# SensorsActuators.net
KiCad netlist of a schematic drawn in Altium Designer
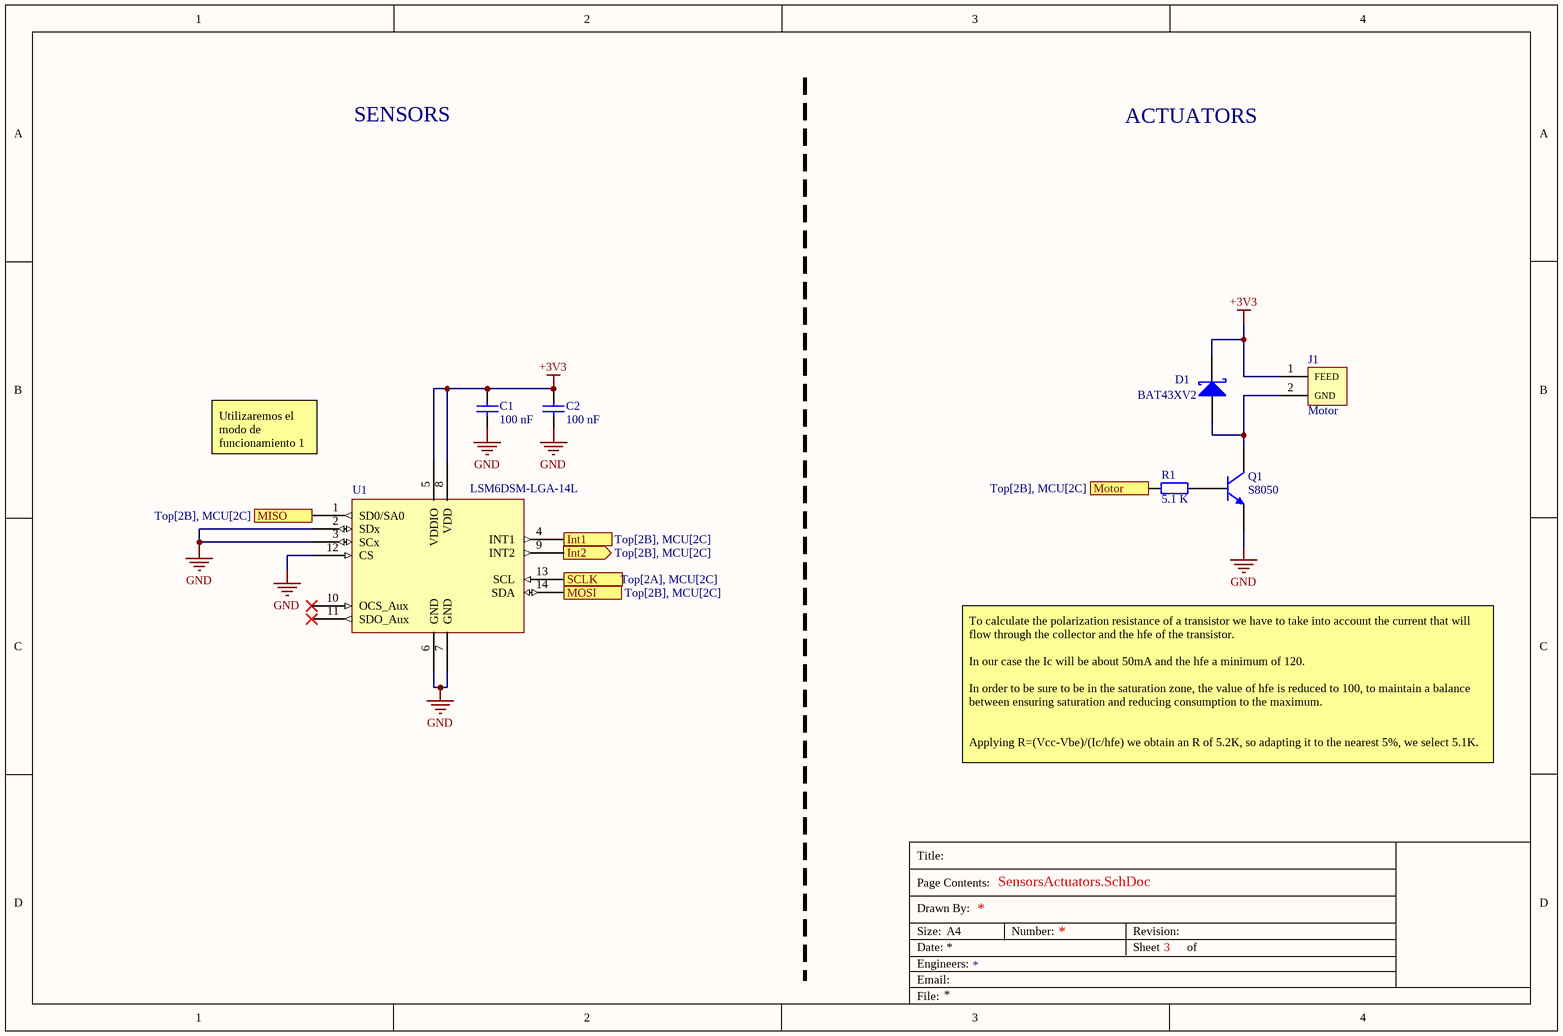
[diagram p0: SensorsActuators.SchDoc]

(export (version "E")
  (design (tool "Eeschema 10.0.6"))
  (components
    (comp (ref "C1")
      (value "100 nF")
      (footprint "C0402")
      (description "Capacitor")
      (libsource (lib "DEOP2324") (part "C"))
    )
    (comp (ref "C2")
      (value "100 nF")
      (footprint "C0402")
      (description "Capacitor")
      (libsource (lib "DEOP2324") (part "C"))
    )
    (comp (ref "D1")
      (value "BAT43XV2")
      (footprint "SOD_523")
      (description "Schottky Diode")
      (libsource (lib "DEOP2324") (part "D Schottky"))
    )
    (comp (ref "J1")
      (value "Motor")
      (footprint "Hand solder wire polarity")
      (libsource (lib "DEOP2324") (part "Motor"))
    )
    (comp (ref "Q1")
      (value "S8050")
      (footprint "SOT23")
      (description "NPN Bipolar Transistor")
      (libsource (lib "DEOP2324") (part "NPN"))
    )
    (comp (ref "R1")
      (value "5.1 K")
      (footprint "R0402")
      (description "Resistor")
      (libsource (lib "DEOP2324") (part "R"))
    )
    (comp (ref "U1")
      (value "LSM6DSM-LGA-14L")
      (footprint "LSM6DSM-LGA-14L-v2")
      (description "6-axis IMU, Accel&Gyro")
      (libsource (lib "DEOP2324") (part "LSM6DSM-LGA-14L"))
    )
  )
  (nets
    (net (code "1") (name "+3V3") (class "Default")
      (node (ref "C1") (pin "1") (pinfunction "1_1") (pintype "passive"))
      (node (ref "C2") (pin "1") (pinfunction "1_1") (pintype "passive"))
      (node (ref "D1") (pin "2") (pinfunction "K_2") (pintype "passive"))
      (node (ref "J1") (pin "1") (pinfunction "FEED_1") (pintype "power_in"))
      (node (ref "U1") (pin "5") (pinfunction "VDDIO_5") (pintype "power_in"))
      (node (ref "U1") (pin "8") (pinfunction "VDD_8") (pintype "power_in"))
    )
    (net (code "2") (name "/Int1") (class "Default")
      (node (ref "U1") (pin "4") (pinfunction "INT1_4") (pintype "output"))
    )
    (net (code "3") (name "/Int2") (class "Default")
      (node (ref "U1") (pin "9") (pinfunction "INT2_9") (pintype "output"))
    )
    (net (code "4") (name "/MISO") (class "Default")
      (node (ref "U1") (pin "1") (pinfunction "SD0/SA0_1") (pintype "output"))
    )
    (net (code "5") (name "/MOSI") (class "Default")
      (node (ref "U1") (pin "14") (pinfunction "SDA_14") (pintype "bidirectional"))
    )
    (net (code "6") (name "/Motor") (class "Default")
      (node (ref "R1") (pin "1") (pinfunction "1_1") (pintype "passive"))
    )
    (net (code "7") (name "/SCLK") (class "Default")
      (node (ref "U1") (pin "13") (pinfunction "SCL_13") (pintype "input"))
    )
    (net (code "8") (name "GND") (class "Default")
      (node (ref "C1") (pin "2") (pinfunction "2_2") (pintype "passive"))
      (node (ref "C2") (pin "2") (pinfunction "2_2") (pintype "passive"))
      (node (ref "Q1") (pin "2") (pinfunction "E_2") (pintype "passive"))
      (node (ref "U1") (pin "12") (pinfunction "CS_12") (pintype "input"))
      (node (ref "U1") (pin "2") (pinfunction "SDx_2") (pintype "bidirectional"))
      (node (ref "U1") (pin "3") (pinfunction "SCx_3") (pintype "bidirectional"))
      (node (ref "U1") (pin "6") (pinfunction "GND_6") (pintype "power_in"))
      (node (ref "U1") (pin "7") (pinfunction "GND_7") (pintype "power_in"))
    )
    (net (code "9") (name "Net-(D1-A)") (class "Default")
      (node (ref "D1") (pin "1") (pinfunction "A_1") (pintype "passive"))
      (node (ref "J1") (pin "2") (pinfunction "GND_2") (pintype "power_in"))
      (node (ref "Q1") (pin "3") (pinfunction "C_3") (pintype "passive"))
    )
    (net (code "10") (name "Net-(Q1-B)") (class "Default")
      (node (ref "Q1") (pin "1") (pinfunction "B_1") (pintype "passive"))
      (node (ref "R1") (pin "2") (pinfunction "2_2") (pintype "passive"))
    )
    (net (code "11") (name "unconnected-(U1-OCS_Aux-Pad10)") (class "Default")
      (node (ref "U1") (pin "10") (pinfunction "OCS_Aux_10") (pintype "input+no_connect"))
    )
    (net (code "12") (name "unconnected-(U1-SDO_Aux-Pad11)") (class "Default")
      (node (ref "U1") (pin "11") (pinfunction "SDO_Aux_11") (pintype "output+no_connect"))
    )
  )
)
